# WebCamera.net
KiCad netlist of a schematic drawn in Altium Designer
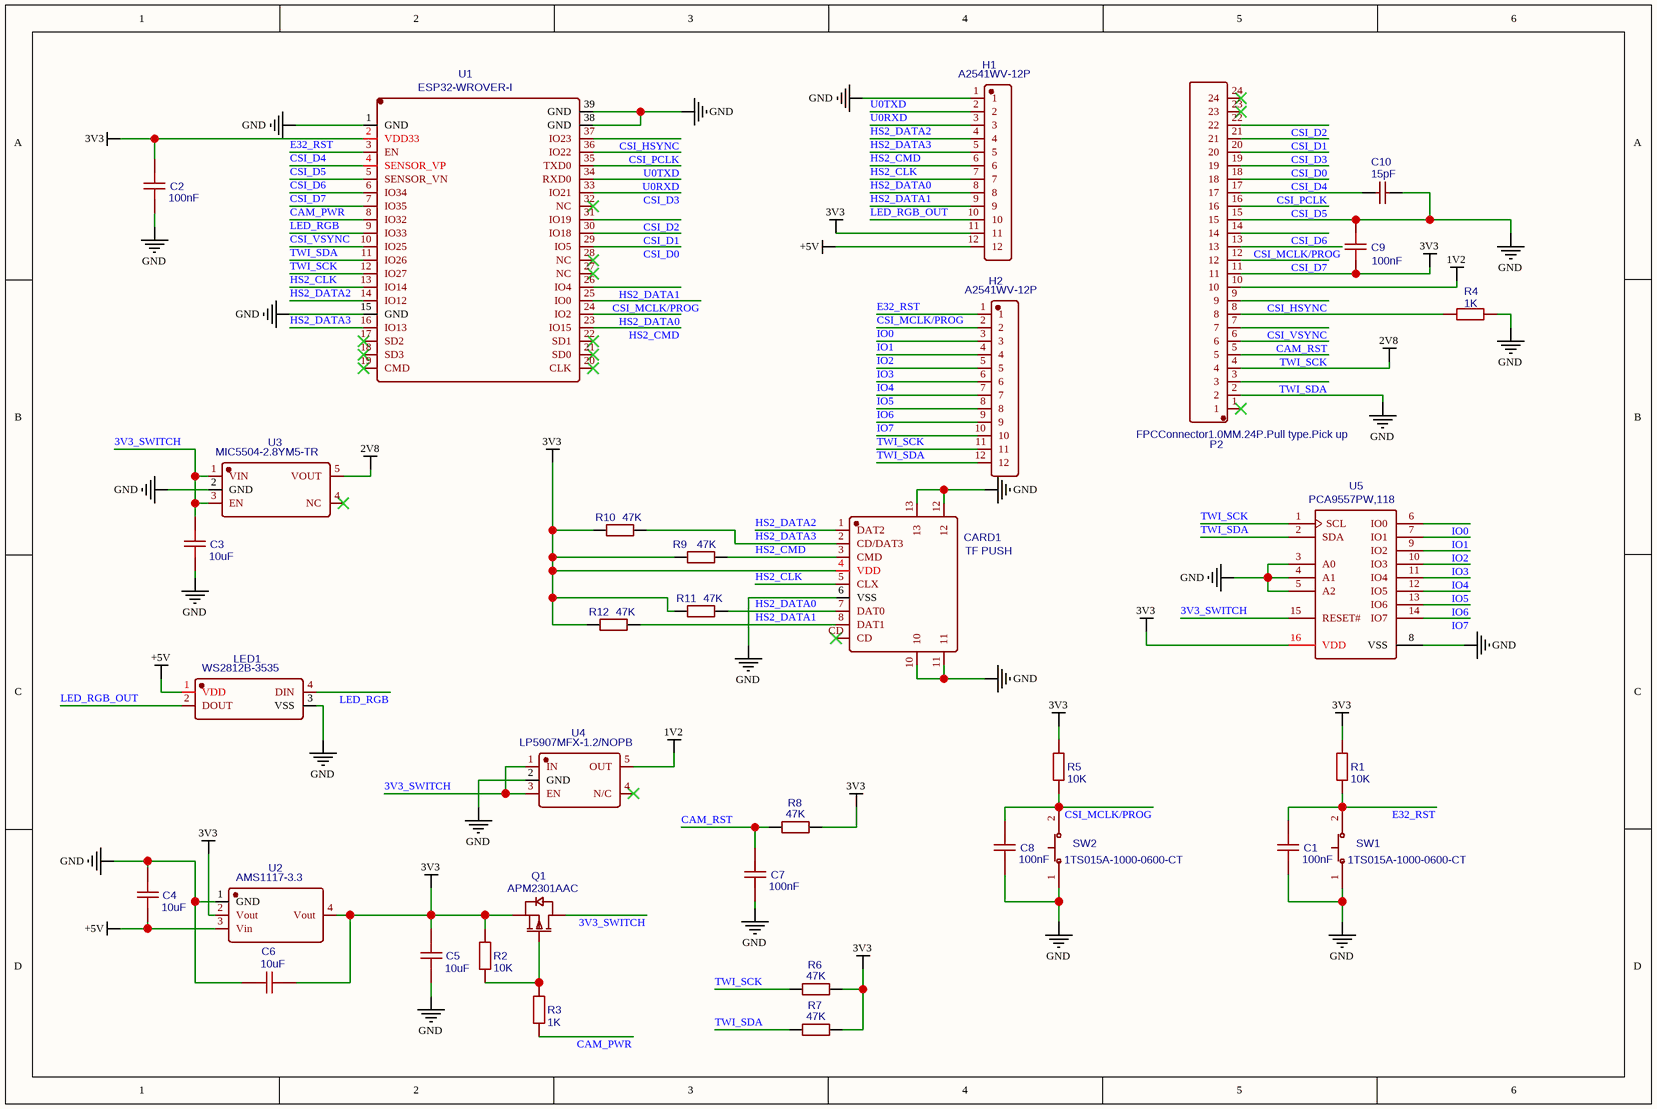
[diagram p0: WebCamera.schdoc]

(export (version "E")
  (design (tool "Eeschema 10.0.6"))
  (components
    (comp (ref "C1")
      (value "100nF")
      (fields
        (field (name "BOM_SUPPLIER PART") "C307331")
        (field (name "BOM_MANUFACTURER PART") "CL05B104KB54PNC")
        (field (name "CONTRIBUTOR") "LCSC")
      )
      (libsource (lib "altium-import") (part "root_1_100nF_"))
    )
    (comp (ref "C2")
      (value "100nF")
      (fields
        (field (name "BOM_SUPPLIER PART") "C307331")
        (field (name "BOM_MANUFACTURER PART") "CL05B104KB54PNC")
        (field (name "CONTRIBUTOR") "LCSC")
      )
      (libsource (lib "altium-import") (part "root_1_100nF_"))
    )
    (comp (ref "C3")
      (value "10uF")
      (fields
        (field (name "BOM_MANUFACTURER PART") "CL10A106KP8NNNC")
        (field (name "BOM_SUPPLIER PART") "C19702")
      )
      (libsource (lib "altium-import") (part "root_1_10uF_"))
    )
    (comp (ref "C4")
      (value "10uF")
      (fields
        (field (name "BOM_MANUFACTURER PART") "CL10A106KP8NNNC")
        (field (name "BOM_SUPPLIER PART") "C19702")
      )
      (libsource (lib "altium-import") (part "root_1_10uF_"))
    )
    (comp (ref "C5")
      (value "10uF")
      (fields
        (field (name "BOM_MANUFACTURER PART") "CL10A106KP8NNNC")
        (field (name "BOM_SUPPLIER PART") "C19702")
      )
      (libsource (lib "altium-import") (part "root_1_10uF_"))
    )
    (comp (ref "C6")
      (value "10uF")
      (fields
        (field (name "BOM_MANUFACTURER PART") "CL10A106KP8NNNC")
        (field (name "BOM_SUPPLIER PART") "C19702")
      )
      (libsource (lib "altium-import") (part "root_2_10uF_"))
    )
    (comp (ref "C7")
      (value "100nF")
      (fields
        (field (name "BOM_SUPPLIER PART") "C307331")
        (field (name "BOM_MANUFACTURER PART") "CL05B104KB54PNC")
        (field (name "CONTRIBUTOR") "LCSC")
      )
      (libsource (lib "altium-import") (part "root_1_100nF_"))
    )
    (comp (ref "C8")
      (value "100nF")
      (fields
        (field (name "BOM_SUPPLIER PART") "C307331")
        (field (name "BOM_MANUFACTURER PART") "CL05B104KB54PNC")
        (field (name "CONTRIBUTOR") "LCSC")
      )
      (libsource (lib "altium-import") (part "root_1_100nF_"))
    )
    (comp (ref "C9")
      (value "100nF")
      (fields
        (field (name "BOM_SUPPLIER PART") "C307331")
        (field (name "BOM_MANUFACTURER PART") "CL05B104KB54PNC")
        (field (name "CONTRIBUTOR") "LCSC")
      )
      (libsource (lib "altium-import") (part "root_1_100nF_"))
    )
    (comp (ref "C10")
      (value "15pF")
      (fields
        (field (name "BOM_MANUFACTURER PART") "0402CG150J500NT")
        (field (name "BOM_SUPPLIER PART") "C1548")
      )
      (libsource (lib "altium-import") (part "root_2_15pF_"))
    )
    (comp (ref "CARD1")
      (value "TF PUSH")
      (fields (field (name "BOM_SUPPLIER PART") "C393941") (field (name "CONTRIBUTOR") "LCSC"))
      (libsource (lib "altium-import") (part "root_0_TF PUSH_"))
    )
    (comp (ref "H1")
      (value "A2541WV-12P")
      (fields (field (name "BOM_SUPPLIER PART") "C225487") (field (name "CONTRIBUTOR") "LCSC"))
      (libsource (lib "altium-import") (part "root_1_A2541WV-12P_"))
    )
    (comp (ref "H2")
      (value "A2541WV-12P")
      (fields (field (name "BOM_SUPPLIER PART") "C225487") (field (name "CONTRIBUTOR") "LCSC"))
      (libsource (lib "altium-import") (part "root_1_A2541WV-12P_"))
    )
    (comp (ref "LED1")
      (value "WS2812B-3535")
      (fields (field (name "BOM_SUPPLIER PART") "C114583") (field (name "CONTRIBUTOR") "LCSC"))
      (libsource (lib "altium-import") (part "root_0_WS2812B-3535_"))
    )
    (comp (ref "P2")
      (value "FPCConnector1.0MM.24P.Pull type.Pick up")
      (fields (field (name "BOM_SUPPLIER PART") "C34750"))
      (libsource (lib "altium-import") (part "root_0_FPCConnector1.0MM.24P.Pull type.Pick up_"))
    )
    (comp (ref "Q1")
      (value "APM2301AAC")
      (fields (field (name "BOM_SUPPLIER PART") "C475607") (field (name "CONTRIBUTOR") "LCSC"))
      (libsource (lib "altium-import") (part "root_1_APM2301AAC_"))
    )
    (comp (ref "R1")
      (value "10K")
      (fields
        (field (name "BOM_SUPPLIER PART") "C380776")
        (field (name "BOM_MANUFACTURER PART") "SY0805JN10KP")
        (field (name "CONTRIBUTOR") "LCSC")
      )
      (libsource (lib "altium-import") (part "root_1_10K_"))
    )
    (comp (ref "R2")
      (value "10K")
      (fields
        (field (name "BOM_SUPPLIER PART") "C380776")
        (field (name "BOM_MANUFACTURER PART") "SY0805JN10KP")
        (field (name "CONTRIBUTOR") "LCSC")
      )
      (libsource (lib "altium-import") (part "root_1_10K_"))
    )
    (comp (ref "R3")
      (value "1K")
      (fields
        (field (name "BOM_SUPPLIER PART") "C328385")
        (field (name "BOM_MANUFACTURER PART") "AECR0805F1K00K9")
        (field (name "CONTRIBUTOR") "LCSC")
      )
      (libsource (lib "altium-import") (part "root_1_1K_"))
    )
    (comp (ref "R4")
      (value "1K")
      (fields
        (field (name "BOM_SUPPLIER PART") "C328385")
        (field (name "BOM_MANUFACTURER PART") "AECR0805F1K00K9")
        (field (name "CONTRIBUTOR") "LCSC")
      )
      (libsource (lib "altium-import") (part "root_2_1K_"))
    )
    (comp (ref "R5")
      (value "10K")
      (fields
        (field (name "BOM_SUPPLIER PART") "C380776")
        (field (name "BOM_MANUFACTURER PART") "SY0805JN10KP")
        (field (name "CONTRIBUTOR") "LCSC")
      )
      (libsource (lib "altium-import") (part "root_1_10K_"))
    )
    (comp (ref "R6")
      (value "47K")
      (fields
        (field (name "BOM_MANUFACTURER PART") "CR0805J80473G")
        (field (name "BOM_SUPPLIER PART") "C102018")
      )
      (libsource (lib "altium-import") (part "root_0_47K_"))
    )
    (comp (ref "R7")
      (value "47K")
      (fields
        (field (name "BOM_MANUFACTURER PART") "CR0805J80473G")
        (field (name "BOM_SUPPLIER PART") "C102018")
      )
      (libsource (lib "altium-import") (part "root_0_47K_"))
    )
    (comp (ref "R8")
      (value "47K")
      (fields
        (field (name "BOM_MANUFACTURER PART") "CR0805J80473G")
        (field (name "BOM_SUPPLIER PART") "C102018")
      )
      (libsource (lib "altium-import") (part "root_0_47K_"))
    )
    (comp (ref "R9")
      (value "47K")
      (fields
        (field (name "BOM_MANUFACTURER PART") "CR0805J80473G")
        (field (name "BOM_SUPPLIER PART") "C102018")
      )
      (libsource (lib "altium-import") (part "root_2_47K_"))
    )
    (comp (ref "R10")
      (value "47K")
      (fields
        (field (name "BOM_MANUFACTURER PART") "CR0805J80473G")
        (field (name "BOM_SUPPLIER PART") "C102018")
      )
      (libsource (lib "altium-import") (part "root_2_47K_"))
    )
    (comp (ref "R11")
      (value "47K")
      (fields
        (field (name "BOM_MANUFACTURER PART") "CR0805J80473G")
        (field (name "BOM_SUPPLIER PART") "C102018")
      )
      (libsource (lib "altium-import") (part "root_2_47K_"))
    )
    (comp (ref "R12")
      (value "47K")
      (fields
        (field (name "BOM_MANUFACTURER PART") "CR0805J80473G")
        (field (name "BOM_SUPPLIER PART") "C102018")
      )
      (libsource (lib "altium-import") (part "root_2_47K_"))
    )
    (comp (ref "SW1")
      (value "1TS015A-1000-0600-CT")
      (fields (field (name "BOM_SUPPLIER PART") "C398744") (field (name "CONTRIBUTOR") "LCSC"))
      (libsource (lib "altium-import") (part "root_1_1TS015A-1000-0600-CT_"))
    )
    (comp (ref "SW2")
      (value "1TS015A-1000-0600-CT")
      (fields (field (name "BOM_SUPPLIER PART") "C398744") (field (name "CONTRIBUTOR") "LCSC"))
      (libsource (lib "altium-import") (part "root_1_1TS015A-1000-0600-CT_"))
    )
    (comp (ref "U1")
      (value "ESP32-WROVER-I")
      (fields (field (name "BOM_SUPPLIER PART") "C132370") (field (name "CONTRIBUTOR") "LCSC"))
      (libsource (lib "altium-import") (part "root_0_ESP32-WROVER-I_"))
    )
    (comp (ref "U2")
      (value "AMS1117-3.3")
      (fields (field (name "BOM_SUPPLIER PART") "C6186"))
      (libsource (lib "altium-import") (part "root_0_AMS1117-3.3_"))
    )
    (comp (ref "U3")
      (value "MIC5504-2.8YM5-TR")
      (fields (field (name "BOM_SUPPLIER PART") "C95749") (field (name "CONTRIBUTOR") "LCSC"))
      (libsource (lib "altium-import") (part "root_0_MIC5504-2.8YM5-TR_"))
    )
    (comp (ref "U4")
      (value "LP5907MFX-1.2/NOPB")
      (fields (field (name "BOM_SUPPLIER PART") "C73478") (field (name "CONTRIBUTOR") "LCSC"))
      (libsource (lib "altium-import") (part "root_0_LP5907MFX-1.2/NOPB_"))
    )
    (comp (ref "U5")
      (value "PCA9557PW,118")
      (fields (field (name "BOM_SUPPLIER PART") "C141380") (field (name "CONTRIBUTOR") "LCSC"))
      (libsource (lib "altium-import") (part "root_0_PCA9557PW,118_"))
    )
  )
  (nets
    (net (code "1") (name "+5V") (class "Default")
      (node (ref "C4") (pin "1") (pinfunction "1_1") (pintype "passive"))
      (node (ref "H1") (pin "12") (pinfunction "12_12") (pintype "passive"))
      (node (ref "LED1") (pin "1") (pinfunction "VDD_1") (pintype "passive"))
      (node (ref "U2") (pin "3") (pinfunction "Vin_3") (pintype "passive"))
    )
    (net (code "2") (name "/3V3_SWITCH") (class "Default")
      (node (ref "C3") (pin "2") (pinfunction "2_2") (pintype "passive"))
      (node (ref "Q1") (pin "3") (pinfunction "D_3") (pintype "passive"))
      (node (ref "U3") (pin "1") (pinfunction "VIN_1") (pintype "passive"))
      (node (ref "U3") (pin "3") (pinfunction "EN_3") (pintype "passive"))
      (node (ref "U4") (pin "1") (pinfunction "IN_1") (pintype "passive"))
      (node (ref "U4") (pin "3") (pinfunction "EN_3") (pintype "passive"))
      (node (ref "U5") (pin "15") (pinfunction "RESET#_15") (pintype "passive"))
    )
    (net (code "3") (name "/CAM_PWR") (class "Default")
      (node (ref "R3") (pin "1") (pinfunction "1_1") (pintype "passive"))
      (node (ref "U1") (pin "8") (pinfunction "IO32_8") (pintype "passive"))
    )
    (net (code "4") (name "/CAM_RST") (class "Default")
      (node (ref "C7") (pin "1") (pinfunction "1_1") (pintype "passive"))
      (node (ref "P2") (pin "6") (pinfunction "6_6") (pintype "passive"))
      (node (ref "R8") (pin "1") (pinfunction "1_1") (pintype "passive"))
    )
    (net (code "5") (name "/CSI_D0") (class "Default")
      (node (ref "P2") (pin "19") (pinfunction "19_19") (pintype "passive"))
      (node (ref "U1") (pin "29") (pinfunction "IO5_29") (pintype "passive"))
    )
    (net (code "6") (name "/CSI_D1") (class "Default")
      (node (ref "P2") (pin "21") (pinfunction "21_21") (pintype "passive"))
      (node (ref "U1") (pin "30") (pinfunction "IO18_30") (pintype "passive"))
    )
    (net (code "7") (name "/CSI_D2") (class "Default")
      (node (ref "P2") (pin "22") (pinfunction "22_22") (pintype "passive"))
      (node (ref "U1") (pin "31") (pinfunction "IO19_31") (pintype "passive"))
    )
    (net (code "8") (name "/CSI_D3") (class "Default")
      (node (ref "P2") (pin "20") (pinfunction "20_20") (pintype "passive"))
      (node (ref "U1") (pin "33") (pinfunction "IO21_33") (pintype "passive"))
    )
    (net (code "9") (name "/CSI_D4") (class "Default")
      (node (ref "P2") (pin "18") (pinfunction "18_18") (pintype "passive"))
      (node (ref "U1") (pin "4") (pinfunction "SENSOR_VP_4") (pintype "passive"))
    )
    (net (code "10") (name "/CSI_D5") (class "Default")
      (node (ref "P2") (pin "16") (pinfunction "16_16") (pintype "passive"))
      (node (ref "U1") (pin "5") (pinfunction "SENSOR_VN_5") (pintype "passive"))
    )
    (net (code "11") (name "/CSI_D6") (class "Default")
      (node (ref "P2") (pin "14") (pinfunction "14_14") (pintype "passive"))
      (node (ref "U1") (pin "6") (pinfunction "IO34_6") (pintype "passive"))
    )
    (net (code "12") (name "/CSI_D7") (class "Default")
      (node (ref "P2") (pin "12") (pinfunction "12_12") (pintype "passive"))
      (node (ref "U1") (pin "7") (pinfunction "IO35_7") (pintype "passive"))
    )
    (net (code "13") (name "/CSI_HSYNC") (class "Default")
      (node (ref "P2") (pin "9") (pinfunction "9_9") (pintype "passive"))
      (node (ref "U1") (pin "37") (pinfunction "IO23_37") (pintype "passive"))
    )
    (net (code "14") (name "/CSI_MCLK{slash}PROG") (class "Default")
      (node (ref "C8") (pin "1") (pinfunction "1_1") (pintype "passive"))
      (node (ref "H2") (pin "2") (pinfunction "2_2") (pintype "passive"))
      (node (ref "P2") (pin "13") (pinfunction "13_13") (pintype "passive"))
      (node (ref "R5") (pin "1") (pinfunction "1_1") (pintype "passive"))
      (node (ref "SW2") (pin "2") (pinfunction "2_2") (pintype "passive"))
      (node (ref "U1") (pin "25") (pinfunction "IO0_25") (pintype "passive"))
    )
    (net (code "15") (name "/CSI_PCLK") (class "Default")
      (node (ref "C10") (pin "2") (pinfunction "2_2") (pintype "passive"))
      (node (ref "P2") (pin "17") (pinfunction "17_17") (pintype "passive"))
      (node (ref "U1") (pin "36") (pinfunction "IO22_36") (pintype "passive"))
    )
    (net (code "16") (name "/CSI_VSYNC") (class "Default")
      (node (ref "P2") (pin "7") (pinfunction "7_7") (pintype "passive"))
      (node (ref "U1") (pin "10") (pinfunction "IO25_10") (pintype "passive"))
    )
    (net (code "17") (name "/E32_RST") (class "Default")
      (node (ref "C1") (pin "1") (pinfunction "1_1") (pintype "passive"))
      (node (ref "H2") (pin "1") (pinfunction "1_1") (pintype "passive"))
      (node (ref "R1") (pin "1") (pinfunction "1_1") (pintype "passive"))
      (node (ref "SW1") (pin "2") (pinfunction "2_2") (pintype "passive"))
      (node (ref "U1") (pin "3") (pinfunction "EN_3") (pintype "passive"))
    )
    (net (code "18") (name "/HS2_CLK") (class "Default")
      (node (ref "CARD1") (pin "5") (pinfunction "CLX_5") (pintype "passive"))
      (node (ref "H1") (pin "7") (pinfunction "7_7") (pintype "passive"))
      (node (ref "U1") (pin "13") (pinfunction "IO14_13") (pintype "passive"))
    )
    (net (code "19") (name "/HS2_CMD") (class "Default")
      (node (ref "CARD1") (pin "3") (pinfunction "CMD_3") (pintype "passive"))
      (node (ref "H1") (pin "6") (pinfunction "6_6") (pintype "passive"))
      (node (ref "R9") (pin "1") (pinfunction "1_1") (pintype "passive"))
      (node (ref "U1") (pin "23") (pinfunction "IO15_23") (pintype "passive"))
    )
    (net (code "20") (name "/HS2_DATA0") (class "Default")
      (node (ref "CARD1") (pin "7") (pinfunction "DAT0_7") (pintype "passive"))
      (node (ref "H1") (pin "8") (pinfunction "8_8") (pintype "passive"))
      (node (ref "R11") (pin "1") (pinfunction "1_1") (pintype "passive"))
      (node (ref "U1") (pin "24") (pinfunction "IO2_24") (pintype "passive"))
    )
    (net (code "21") (name "/HS2_DATA1") (class "Default")
      (node (ref "CARD1") (pin "8") (pinfunction "DAT1_8") (pintype "passive"))
      (node (ref "H1") (pin "9") (pinfunction "9_9") (pintype "passive"))
      (node (ref "R12") (pin "1") (pinfunction "1_1") (pintype "passive"))
      (node (ref "U1") (pin "26") (pinfunction "IO4_26") (pintype "passive"))
    )
    (net (code "22") (name "/HS2_DATA2") (class "Default")
      (node (ref "CARD1") (pin "1") (pinfunction "DAT2_1") (pintype "passive"))
      (node (ref "H1") (pin "4") (pinfunction "4_4") (pintype "passive"))
      (node (ref "U1") (pin "14") (pinfunction "IO12_14") (pintype "passive"))
    )
    (net (code "23") (name "/HS2_DATA3") (class "Default")
      (node (ref "CARD1") (pin "2") (pinfunction "CD/DAT3_2") (pintype "passive"))
      (node (ref "H1") (pin "5") (pinfunction "5_5") (pintype "passive"))
      (node (ref "R10") (pin "1") (pinfunction "1_1") (pintype "passive"))
      (node (ref "U1") (pin "16") (pinfunction "IO13_16") (pintype "passive"))
    )
    (net (code "24") (name "/IO0") (class "Default")
      (node (ref "H2") (pin "3") (pinfunction "3_3") (pintype "passive"))
      (node (ref "U5") (pin "6") (pinfunction "IO0_6") (pintype "passive"))
    )
    (net (code "25") (name "/IO1") (class "Default")
      (node (ref "H2") (pin "4") (pinfunction "4_4") (pintype "passive"))
      (node (ref "U5") (pin "7") (pinfunction "IO1_7") (pintype "passive"))
    )
    (net (code "26") (name "/IO2") (class "Default")
      (node (ref "H2") (pin "5") (pinfunction "5_5") (pintype "passive"))
      (node (ref "U5") (pin "9") (pinfunction "IO2_9") (pintype "passive"))
    )
    (net (code "27") (name "/IO3") (class "Default")
      (node (ref "H2") (pin "6") (pinfunction "6_6") (pintype "passive"))
      (node (ref "U5") (pin "10") (pinfunction "IO3_10") (pintype "passive"))
    )
    (net (code "28") (name "/IO4") (class "Default")
      (node (ref "H2") (pin "7") (pinfunction "7_7") (pintype "passive"))
      (node (ref "U5") (pin "11") (pinfunction "IO4_11") (pintype "passive"))
    )
    (net (code "29") (name "/IO5") (class "Default")
      (node (ref "H2") (pin "8") (pinfunction "8_8") (pintype "passive"))
      (node (ref "U5") (pin "12") (pinfunction "IO5_12") (pintype "passive"))
    )
    (net (code "30") (name "/IO6") (class "Default")
      (node (ref "H2") (pin "9") (pinfunction "9_9") (pintype "passive"))
      (node (ref "U5") (pin "13") (pinfunction "IO6_13") (pintype "passive"))
    )
    (net (code "31") (name "/IO7") (class "Default")
      (node (ref "H2") (pin "10") (pinfunction "10_10") (pintype "passive"))
      (node (ref "U5") (pin "14") (pinfunction "IO7_14") (pintype "passive"))
    )
    (net (code "32") (name "/LED_RGB") (class "Default")
      (node (ref "LED1") (pin "4") (pinfunction "DIN_4") (pintype "passive"))
      (node (ref "U1") (pin "9") (pinfunction "IO33_9") (pintype "passive"))
    )
    (net (code "33") (name "/LED_RGB_OUT") (class "Default")
      (node (ref "H1") (pin "10") (pinfunction "10_10") (pintype "passive"))
      (node (ref "LED1") (pin "2") (pinfunction "DOUT_2") (pintype "passive"))
    )
    (net (code "34") (name "/TWI_SCK") (class "Default")
      (node (ref "H2") (pin "11") (pinfunction "11_11") (pintype "passive"))
      (node (ref "P2") (pin "5") (pinfunction "5_5") (pintype "passive"))
      (node (ref "R6") (pin "1") (pinfunction "1_1") (pintype "passive"))
      (node (ref "U1") (pin "12") (pinfunction "IO27_12") (pintype "passive"))
      (node (ref "U5") (pin "1") (pinfunction "SCL_1") (pintype "passive"))
    )
    (net (code "35") (name "/TWI_SDA") (class "Default")
      (node (ref "H2") (pin "12") (pinfunction "12_12") (pintype "passive"))
      (node (ref "P2") (pin "3") (pinfunction "3_3") (pintype "passive"))
      (node (ref "R7") (pin "1") (pinfunction "1_1") (pintype "passive"))
      (node (ref "U1") (pin "11") (pinfunction "IO26_11") (pintype "passive"))
      (node (ref "U5") (pin "2") (pinfunction "SDA_2") (pintype "passive"))
    )
    (net (code "36") (name "/U0RXD") (class "Default")
      (node (ref "H1") (pin "3") (pinfunction "3_3") (pintype "passive"))
      (node (ref "U1") (pin "34") (pinfunction "RXD0_34") (pintype "passive"))
    )
    (net (code "37") (name "/U0TXD") (class "Default")
      (node (ref "H1") (pin "2") (pinfunction "2_2") (pintype "passive"))
      (node (ref "U1") (pin "35") (pinfunction "TXD0_35") (pintype "passive"))
    )
    (net (code "38") (name "1V2") (class "Default")
      (node (ref "P2") (pin "10") (pinfunction "10_10") (pintype "passive"))
      (node (ref "U4") (pin "5") (pinfunction "OUT_5") (pintype "passive"))
    )
    (net (code "39") (name "2V8") (class "Default")
      (node (ref "P2") (pin "4") (pinfunction "4_4") (pintype "passive"))
      (node (ref "U3") (pin "5") (pinfunction "VOUT_5") (pintype "passive"))
    )
    (net (code "40") (name "3V3") (class "Default")
      (node (ref "C2") (pin "1") (pinfunction "1_1") (pintype "passive"))
      (node (ref "C5") (pin "2") (pinfunction "2_2") (pintype "passive"))
      (node (ref "C6") (pin "1") (pinfunction "1_1") (pintype "passive"))
      (node (ref "C9") (pin "2") (pinfunction "2_2") (pintype "passive"))
      (node (ref "CARD1") (pin "4") (pinfunction "VDD_4") (pintype "passive"))
      (node (ref "H1") (pin "11") (pinfunction "11_11") (pintype "passive"))
      (node (ref "P2") (pin "11") (pinfunction "11_11") (pintype "passive"))
      (node (ref "Q1") (pin "2") (pinfunction "S_2") (pintype "passive"))
      (node (ref "R1") (pin "2") (pinfunction "2_2") (pintype "passive"))
      (node (ref "R10") (pin "2") (pinfunction "2_2") (pintype "passive"))
      (node (ref "R11") (pin "2") (pinfunction "2_2") (pintype "passive"))
      (node (ref "R12") (pin "2") (pinfunction "2_2") (pintype "passive"))
      (node (ref "R2") (pin "2") (pinfunction "2_2") (pintype "passive"))
      (node (ref "R5") (pin "2") (pinfunction "2_2") (pintype "passive"))
      (node (ref "R6") (pin "2") (pinfunction "2_2") (pintype "passive"))
      (node (ref "R7") (pin "2") (pinfunction "2_2") (pintype "passive"))
      (node (ref "R8") (pin "2") (pinfunction "2_2") (pintype "passive"))
      (node (ref "R9") (pin "2") (pinfunction "2_2") (pintype "passive"))
      (node (ref "U1") (pin "2") (pinfunction "VDD33_2") (pintype "passive"))
      (node (ref "U2") (pin "2") (pinfunction "Vout_2") (pintype "passive"))
      (node (ref "U2") (pin "4") (pinfunction "Vout_4") (pintype "passive"))
      (node (ref "U5") (pin "16") (pinfunction "VDD_16") (pintype "passive"))
    )
    (net (code "41") (name "GND") (class "Default")
      (node (ref "C1") (pin "2") (pinfunction "2_2") (pintype "passive"))
      (node (ref "C10") (pin "1") (pinfunction "1_1") (pintype "passive"))
      (node (ref "C2") (pin "2") (pinfunction "2_2") (pintype "passive"))
      (node (ref "C3") (pin "1") (pinfunction "1_1") (pintype "passive"))
      (node (ref "C4") (pin "2") (pinfunction "2_2") (pintype "passive"))
      (node (ref "C5") (pin "1") (pinfunction "1_1") (pintype "passive"))
      (node (ref "C6") (pin "2") (pinfunction "2_2") (pintype "passive"))
      (node (ref "C7") (pin "2") (pinfunction "2_2") (pintype "passive"))
      (node (ref "C8") (pin "2") (pinfunction "2_2") (pintype "passive"))
      (node (ref "C9") (pin "1") (pinfunction "1_1") (pintype "passive"))
      (node (ref "CARD1") (pin "10") (pinfunction "10_10") (pintype "passive"))
      (node (ref "CARD1") (pin "11") (pinfunction "11_11") (pintype "passive"))
      (node (ref "CARD1") (pin "12") (pinfunction "12_12") (pintype "passive"))
      (node (ref "CARD1") (pin "13") (pinfunction "13_13") (pintype "passive"))
      (node (ref "CARD1") (pin "6") (pinfunction "VSS_6") (pintype "passive"))
      (node (ref "H1") (pin "1") (pinfunction "1_1") (pintype "passive"))
      (node (ref "LED1") (pin "3") (pinfunction "VSS_3") (pintype "passive"))
      (node (ref "P2") (pin "15") (pinfunction "15_15") (pintype "passive"))
      (node (ref "P2") (pin "2") (pinfunction "2_2") (pintype "passive"))
      (node (ref "R4") (pin "1") (pinfunction "1_1") (pintype "passive"))
      (node (ref "SW1") (pin "1") (pinfunction "1_1") (pintype "passive"))
      (node (ref "SW2") (pin "1") (pinfunction "1_1") (pintype "passive"))
      (node (ref "U1") (pin "1") (pinfunction "GND_1") (pintype "passive"))
      (node (ref "U1") (pin "15") (pinfunction "GND_15") (pintype "passive"))
      (node (ref "U1") (pin "38") (pinfunction "GND_38") (pintype "passive"))
      (node (ref "U1") (pin "39") (pinfunction "GND_39") (pintype "passive"))
      (node (ref "U2") (pin "1") (pinfunction "GND_1") (pintype "passive"))
      (node (ref "U3") (pin "2") (pinfunction "GND_2") (pintype "passive"))
      (node (ref "U4") (pin "2") (pinfunction "GND_2") (pintype "passive"))
      (node (ref "U5") (pin "3") (pinfunction "A0_3") (pintype "passive"))
      (node (ref "U5") (pin "4") (pinfunction "A1_4") (pintype "passive"))
      (node (ref "U5") (pin "5") (pinfunction "A2_5") (pintype "passive"))
      (node (ref "U5") (pin "8") (pinfunction "VSS_8") (pintype "passive"))
    )
    (net (code "42") (name "Net-(P2-Pad8)") (class "Default")
      (node (ref "P2") (pin "8") (pinfunction "8_8") (pintype "passive"))
      (node (ref "R4") (pin "2") (pinfunction "2_2") (pintype "passive"))
    )
    (net (code "43") (name "Net-(Q1-G)") (class "Default")
      (node (ref "Q1") (pin "1") (pinfunction "G_1") (pintype "passive"))
      (node (ref "R2") (pin "1") (pinfunction "1_1") (pintype "passive"))
      (node (ref "R3") (pin "2") (pinfunction "2_2") (pintype "passive"))
    )
    (net (code "44") (name "unconnected-(CARD1-PadCD)") (class "Default")
      (node (ref "CARD1") (pin "CD") (pinfunction "CD_CD") (pintype "passive+no_connect"))
    )
    (net (code "45") (name "unconnected-(P2-Pad1)") (class "Default")
      (node (ref "P2") (pin "1") (pinfunction "1_1") (pintype "passive+no_connect"))
    )
    (net (code "46") (name "unconnected-(P2-Pad23)") (class "Default")
      (node (ref "P2") (pin "23") (pinfunction "23_23") (pintype "passive+no_connect"))
    )
    (net (code "47") (name "unconnected-(P2-Pad24)") (class "Default")
      (node (ref "P2") (pin "24") (pinfunction "24_24") (pintype "passive+no_connect"))
    )
    (net (code "48") (name "unconnected-(U1-CLK-Pad20)") (class "Default")
      (node (ref "U1") (pin "20") (pinfunction "CLK_20") (pintype "passive+no_connect"))
    )
    (net (code "49") (name "unconnected-(U1-CMD-Pad19)") (class "Default")
      (node (ref "U1") (pin "19") (pinfunction "CMD_19") (pintype "passive+no_connect"))
    )
    (net (code "50") (name "unconnected-(U1-NC-Pad27)") (class "Default")
      (node (ref "U1") (pin "27") (pinfunction "NC_27") (pintype "passive+no_connect"))
    )
    (net (code "51") (name "unconnected-(U1-NC-Pad28)") (class "Default")
      (node (ref "U1") (pin "28") (pinfunction "NC_28") (pintype "passive+no_connect"))
    )
    (net (code "52") (name "unconnected-(U1-NC-Pad32)") (class "Default")
      (node (ref "U1") (pin "32") (pinfunction "NC_32") (pintype "passive+no_connect"))
    )
    (net (code "53") (name "unconnected-(U1-SD0-Pad21)") (class "Default")
      (node (ref "U1") (pin "21") (pinfunction "SD0_21") (pintype "passive+no_connect"))
    )
    (net (code "54") (name "unconnected-(U1-SD1-Pad22)") (class "Default")
      (node (ref "U1") (pin "22") (pinfunction "SD1_22") (pintype "passive+no_connect"))
    )
    (net (code "55") (name "unconnected-(U1-SD2-Pad17)") (class "Default")
      (node (ref "U1") (pin "17") (pinfunction "SD2_17") (pintype "passive+no_connect"))
    )
    (net (code "56") (name "unconnected-(U1-SD3-Pad18)") (class "Default")
      (node (ref "U1") (pin "18") (pinfunction "SD3_18") (pintype "passive+no_connect"))
    )
    (net (code "57") (name "unconnected-(U3-NC-Pad4)") (class "Default")
      (node (ref "U3") (pin "4") (pinfunction "NC_4") (pintype "passive+no_connect"))
    )
    (net (code "58") (name "unconnected-(U4-N{slash}C-Pad4)") (class "Default")
      (node (ref "U4") (pin "4") (pinfunction "N/C_4") (pintype "passive+no_connect"))
    )
  )
)
